# Shift_Register_IO_Breakout.net
KiCad netlist of a schematic drawn in EAGLE
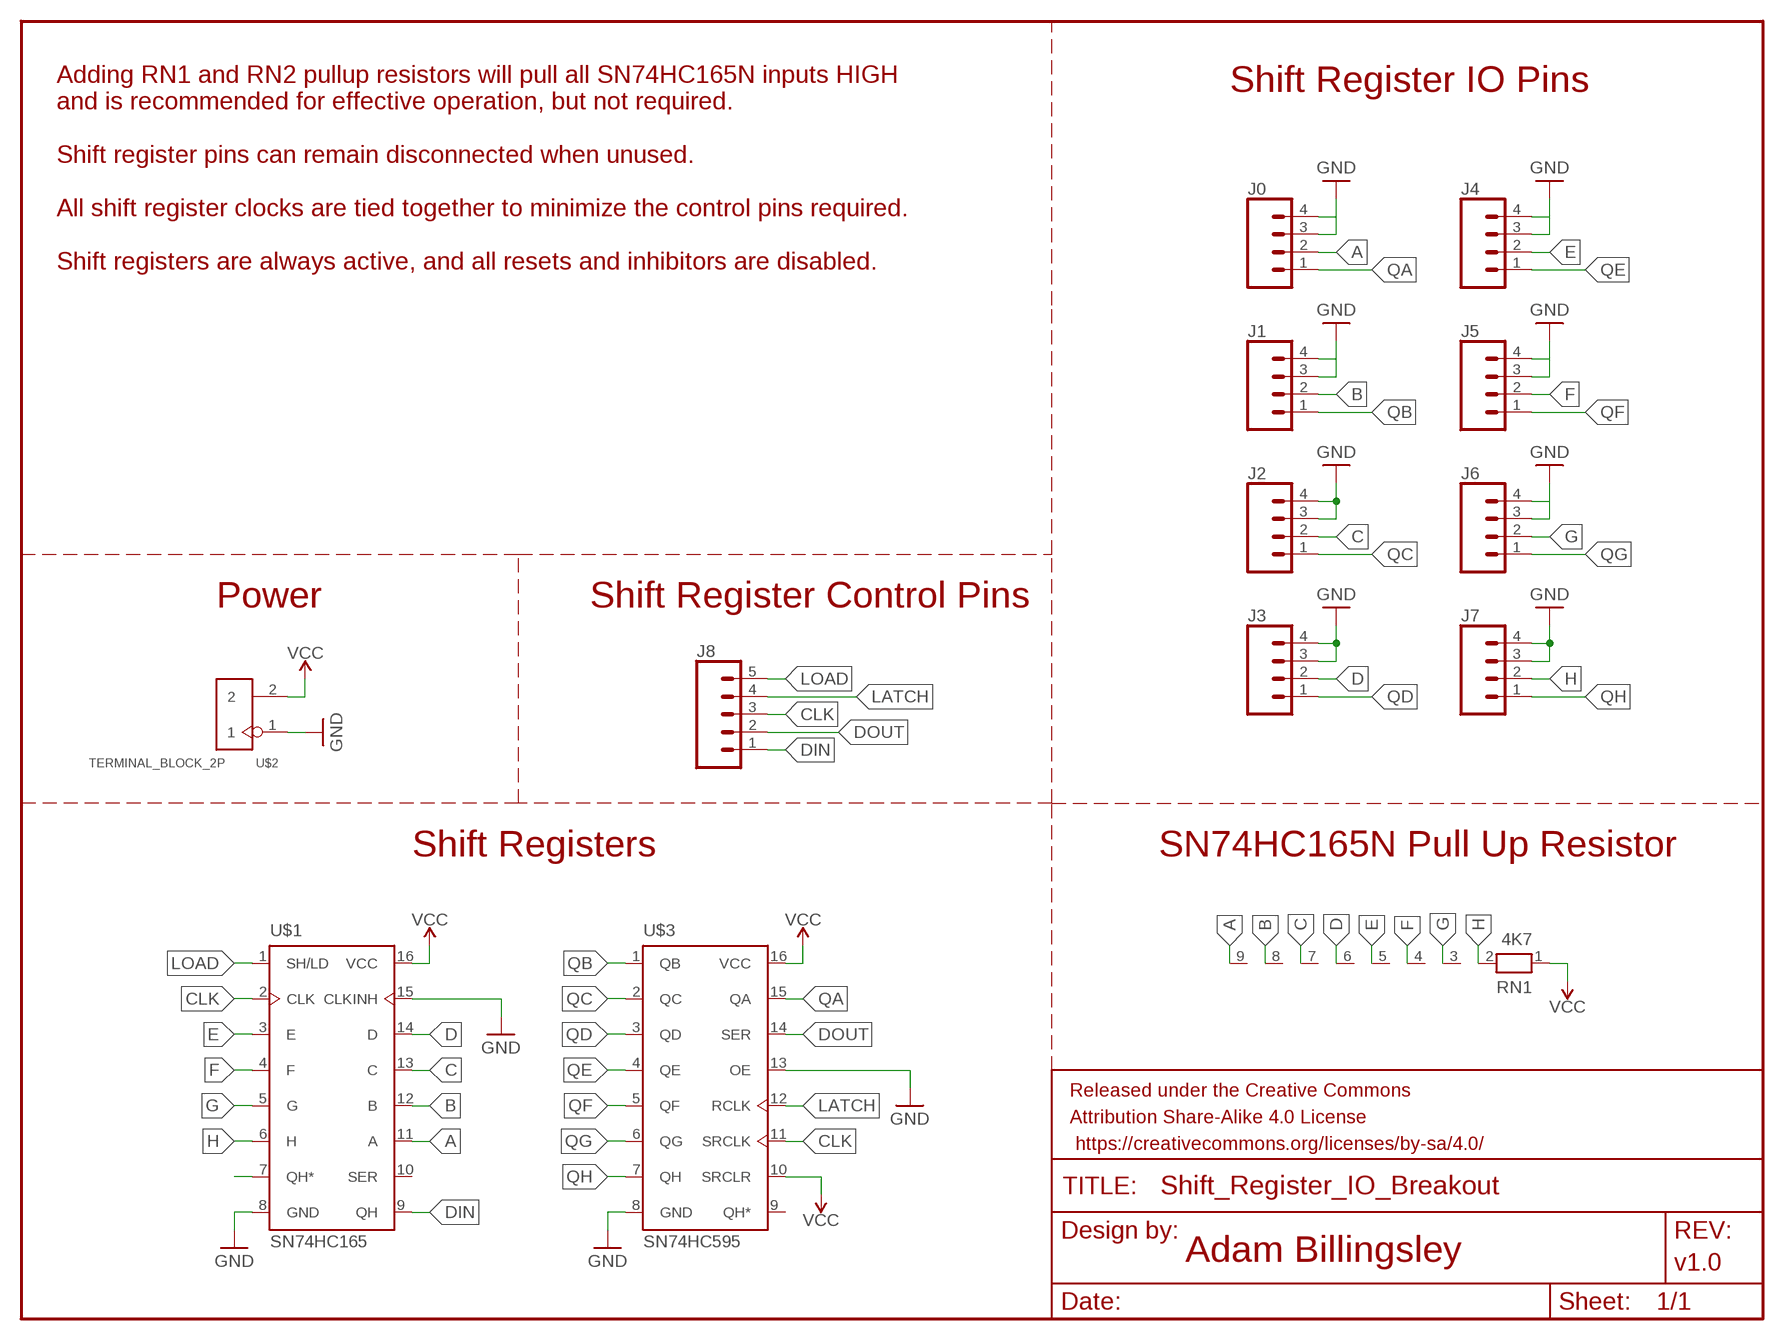
[diagram p0: schematic, sheet 1]

(export (version "E")
  (design (tool "Eeschema 10.0.6"))
  (components
    (comp (ref "FRAME1")
      (value "FRAME-LETTER")
      (footprint "eagle-import:CREATIVE_COMMONS")
      (libsource (lib "eagle-import") (part "FRAME-LETTER"))
    )
    (comp (ref "J0")
      (value "CONN_04")
      (footprint "eagle-import:1X04")
      (libsource (lib "eagle-import") (part "CONN_04"))
    )
    (comp (ref "J1")
      (value "CONN_04")
      (footprint "eagle-import:1X04")
      (libsource (lib "eagle-import") (part "CONN_04"))
    )
    (comp (ref "J2")
      (value "CONN_04")
      (footprint "eagle-import:1X04")
      (libsource (lib "eagle-import") (part "CONN_04"))
    )
    (comp (ref "J3")
      (value "CONN_04")
      (footprint "eagle-import:1X04")
      (libsource (lib "eagle-import") (part "CONN_04"))
    )
    (comp (ref "J4")
      (value "CONN_04")
      (footprint "eagle-import:1X04")
      (libsource (lib "eagle-import") (part "CONN_04"))
    )
    (comp (ref "J5")
      (value "CONN_04")
      (footprint "eagle-import:1X04")
      (libsource (lib "eagle-import") (part "CONN_04"))
    )
    (comp (ref "J6")
      (value "CONN_04")
      (footprint "eagle-import:1X04")
      (libsource (lib "eagle-import") (part "CONN_04"))
    )
    (comp (ref "J7")
      (value "CONN_04")
      (footprint "eagle-import:1X04")
      (libsource (lib "eagle-import") (part "CONN_04"))
    )
    (comp (ref "J8")
      (value "CONN_05")
      (footprint "eagle-import:1X05")
      (libsource (lib "eagle-import") (part "CONN_05"))
    )
    (comp (ref "RN1")
      (value "4K7")
      (footprint "eagle-import:RN-9")
      (libsource (lib "eagle-import") (part "RN08"))
    )
    (comp (ref "U$1")
      (value "SN74HC165")
      (footprint "eagle-import:DIL16")
      (libsource (lib "eagle-import") (part "SN74HC165"))
    )
    (comp (ref "U$2")
      (value "TERMINAL_BLOCK_2P")
      (footprint "eagle-import:H2-5.0-10.5X8.0MM")
      (libsource (lib "eagle-import") (part "TERMINAL_BLOCK_2P"))
    )
    (comp (ref "U$3")
      (value "SN74HC595")
      (footprint "eagle-import:DIL16")
      (libsource (lib "eagle-import") (part "SN74HC595"))
    )
  )
  (nets
    (net (code "1") (name "A") (class "Default")
      (node (ref "J0") (pin "2") (pinfunction "2_2") (pintype "passive"))
      (node (ref "RN1") (pin "9") (pinfunction "9_9") (pintype "passive"))
      (node (ref "U$1") (pin "11") (pinfunction "A_11") (pintype "input"))
    )
    (net (code "2") (name "B") (class "Default")
      (node (ref "J1") (pin "2") (pinfunction "2_2") (pintype "passive"))
      (node (ref "RN1") (pin "8") (pinfunction "8_8") (pintype "passive"))
      (node (ref "U$1") (pin "12") (pinfunction "B_12") (pintype "input"))
    )
    (net (code "3") (name "C") (class "Default")
      (node (ref "J2") (pin "2") (pinfunction "2_2") (pintype "passive"))
      (node (ref "RN1") (pin "7") (pinfunction "7_7") (pintype "passive"))
      (node (ref "U$1") (pin "13") (pinfunction "C_13") (pintype "input"))
    )
    (net (code "4") (name "CLK") (class "Default")
      (node (ref "J8") (pin "3") (pinfunction "3_3") (pintype "passive"))
      (node (ref "U$1") (pin "2") (pinfunction "CLK_2") (pintype "input"))
      (node (ref "U$3") (pin "11") (pinfunction "SRCLK_11") (pintype "input"))
    )
    (net (code "5") (name "D") (class "Default")
      (node (ref "J3") (pin "2") (pinfunction "2_2") (pintype "passive"))
      (node (ref "RN1") (pin "6") (pinfunction "6_6") (pintype "passive"))
      (node (ref "U$1") (pin "14") (pinfunction "D_14") (pintype "input"))
    )
    (net (code "6") (name "DIN") (class "Default")
      (node (ref "J8") (pin "1") (pinfunction "1_1") (pintype "passive"))
      (node (ref "U$1") (pin "9") (pinfunction "QH_9") (pintype "output"))
    )
    (net (code "7") (name "DOUT") (class "Default")
      (node (ref "J8") (pin "2") (pinfunction "2_2") (pintype "passive"))
      (node (ref "U$3") (pin "14") (pinfunction "SER_14") (pintype "input"))
    )
    (net (code "8") (name "E") (class "Default")
      (node (ref "J4") (pin "2") (pinfunction "2_2") (pintype "passive"))
      (node (ref "RN1") (pin "5") (pinfunction "5_5") (pintype "passive"))
      (node (ref "U$1") (pin "3") (pinfunction "E_3") (pintype "input"))
    )
    (net (code "9") (name "F") (class "Default")
      (node (ref "J5") (pin "2") (pinfunction "2_2") (pintype "passive"))
      (node (ref "RN1") (pin "4") (pinfunction "4_4") (pintype "passive"))
      (node (ref "U$1") (pin "4") (pinfunction "F_4") (pintype "input"))
    )
    (net (code "10") (name "G") (class "Default")
      (node (ref "J6") (pin "2") (pinfunction "2_2") (pintype "passive"))
      (node (ref "RN1") (pin "3") (pinfunction "3_3") (pintype "passive"))
      (node (ref "U$1") (pin "5") (pinfunction "G_5") (pintype "input"))
    )
    (net (code "11") (name "GND") (class "Default")
      (node (ref "J0") (pin "3") (pinfunction "3_3") (pintype "passive"))
      (node (ref "J0") (pin "4") (pinfunction "4_4") (pintype "passive"))
      (node (ref "J1") (pin "3") (pinfunction "3_3") (pintype "passive"))
      (node (ref "J1") (pin "4") (pinfunction "4_4") (pintype "passive"))
      (node (ref "J2") (pin "3") (pinfunction "3_3") (pintype "passive"))
      (node (ref "J2") (pin "4") (pinfunction "4_4") (pintype "passive"))
      (node (ref "J3") (pin "3") (pinfunction "3_3") (pintype "passive"))
      (node (ref "J3") (pin "4") (pinfunction "4_4") (pintype "passive"))
      (node (ref "J4") (pin "3") (pinfunction "3_3") (pintype "passive"))
      (node (ref "J4") (pin "4") (pinfunction "4_4") (pintype "passive"))
      (node (ref "J5") (pin "3") (pinfunction "3_3") (pintype "passive"))
      (node (ref "J5") (pin "4") (pinfunction "4_4") (pintype "passive"))
      (node (ref "J6") (pin "3") (pinfunction "3_3") (pintype "passive"))
      (node (ref "J6") (pin "4") (pinfunction "4_4") (pintype "passive"))
      (node (ref "J7") (pin "3") (pinfunction "3_3") (pintype "passive"))
      (node (ref "J7") (pin "4") (pinfunction "4_4") (pintype "passive"))
      (node (ref "U$1") (pin "15") (pinfunction "CLKINH_15") (pintype "input"))
      (node (ref "U$1") (pin "8") (pinfunction "GND_8") (pintype "power_in"))
      (node (ref "U$2") (pin "1") (pinfunction "1_1") (pintype "bidirectional"))
      (node (ref "U$3") (pin "13") (pinfunction "OE_13") (pintype "open_collector"))
      (node (ref "U$3") (pin "8") (pinfunction "GND_8") (pintype "power_in"))
    )
    (net (code "12") (name "H") (class "Default")
      (node (ref "J7") (pin "2") (pinfunction "2_2") (pintype "passive"))
      (node (ref "RN1") (pin "2") (pinfunction "2_2") (pintype "passive"))
      (node (ref "U$1") (pin "6") (pinfunction "H_6") (pintype "input"))
    )
    (net (code "13") (name "LATCH") (class "Default")
      (node (ref "J8") (pin "4") (pinfunction "4_4") (pintype "passive"))
      (node (ref "U$3") (pin "12") (pinfunction "RCLK_12") (pintype "input"))
    )
    (net (code "14") (name "LOAD") (class "Default")
      (node (ref "J8") (pin "5") (pinfunction "5_5") (pintype "passive"))
      (node (ref "U$1") (pin "1") (pinfunction "SH/LD_1") (pintype "open_collector"))
    )
    (net (code "15") (name "QA") (class "Default")
      (node (ref "J0") (pin "1") (pinfunction "1_1") (pintype "passive"))
      (node (ref "U$3") (pin "15") (pinfunction "QA_15") (pintype "output"))
    )
    (net (code "16") (name "QB") (class "Default")
      (node (ref "J1") (pin "1") (pinfunction "1_1") (pintype "passive"))
      (node (ref "U$3") (pin "1") (pinfunction "QB_1") (pintype "output"))
    )
    (net (code "17") (name "QC") (class "Default")
      (node (ref "J2") (pin "1") (pinfunction "1_1") (pintype "passive"))
      (node (ref "U$3") (pin "2") (pinfunction "QC_2") (pintype "output"))
    )
    (net (code "18") (name "QD") (class "Default")
      (node (ref "J3") (pin "1") (pinfunction "1_1") (pintype "passive"))
      (node (ref "U$3") (pin "3") (pinfunction "QD_3") (pintype "output"))
    )
    (net (code "19") (name "QE") (class "Default")
      (node (ref "J4") (pin "1") (pinfunction "1_1") (pintype "passive"))
      (node (ref "U$3") (pin "4") (pinfunction "QE_4") (pintype "output"))
    )
    (net (code "20") (name "QF") (class "Default")
      (node (ref "J5") (pin "1") (pinfunction "1_1") (pintype "passive"))
      (node (ref "U$3") (pin "5") (pinfunction "QF_5") (pintype "output"))
    )
    (net (code "21") (name "QG") (class "Default")
      (node (ref "J6") (pin "1") (pinfunction "1_1") (pintype "passive"))
      (node (ref "U$3") (pin "6") (pinfunction "QG_6") (pintype "output"))
    )
    (net (code "22") (name "QH") (class "Default")
      (node (ref "J7") (pin "1") (pinfunction "1_1") (pintype "passive"))
      (node (ref "U$3") (pin "7") (pinfunction "QH_7") (pintype "output"))
    )
    (net (code "23") (name "VCC") (class "Default")
      (node (ref "RN1") (pin "1") (pinfunction "1_1") (pintype "passive"))
      (node (ref "U$1") (pin "16") (pinfunction "VCC_16") (pintype "power_in"))
      (node (ref "U$2") (pin "2") (pinfunction "2_2") (pintype "bidirectional"))
      (node (ref "U$3") (pin "10") (pinfunction "SRCLR_10") (pintype "open_collector"))
      (node (ref "U$3") (pin "16") (pinfunction "VCC_16") (pintype "power_in"))
    )
    (net (code "24") (name "unconnected-(U$1-QH*-Pad7)") (class "Default")
      (node (ref "U$1") (pin "7") (pinfunction "QH*_7") (pintype "output"))
    )
    (net (code "25") (name "unconnected-(U$1-SER-Pad10)") (class "Default")
      (node (ref "U$1") (pin "10") (pinfunction "SER_10") (pintype "input"))
    )
    (net (code "26") (name "unconnected-(U$3-QH*-Pad9)") (class "Default")
      (node (ref "U$3") (pin "9") (pinfunction "QH*_9") (pintype "output"))
    )
  )
)
